# I2C-7-Segment-Backpack-dot8inch.net
KiCad netlist of a schematic drawn in EAGLE
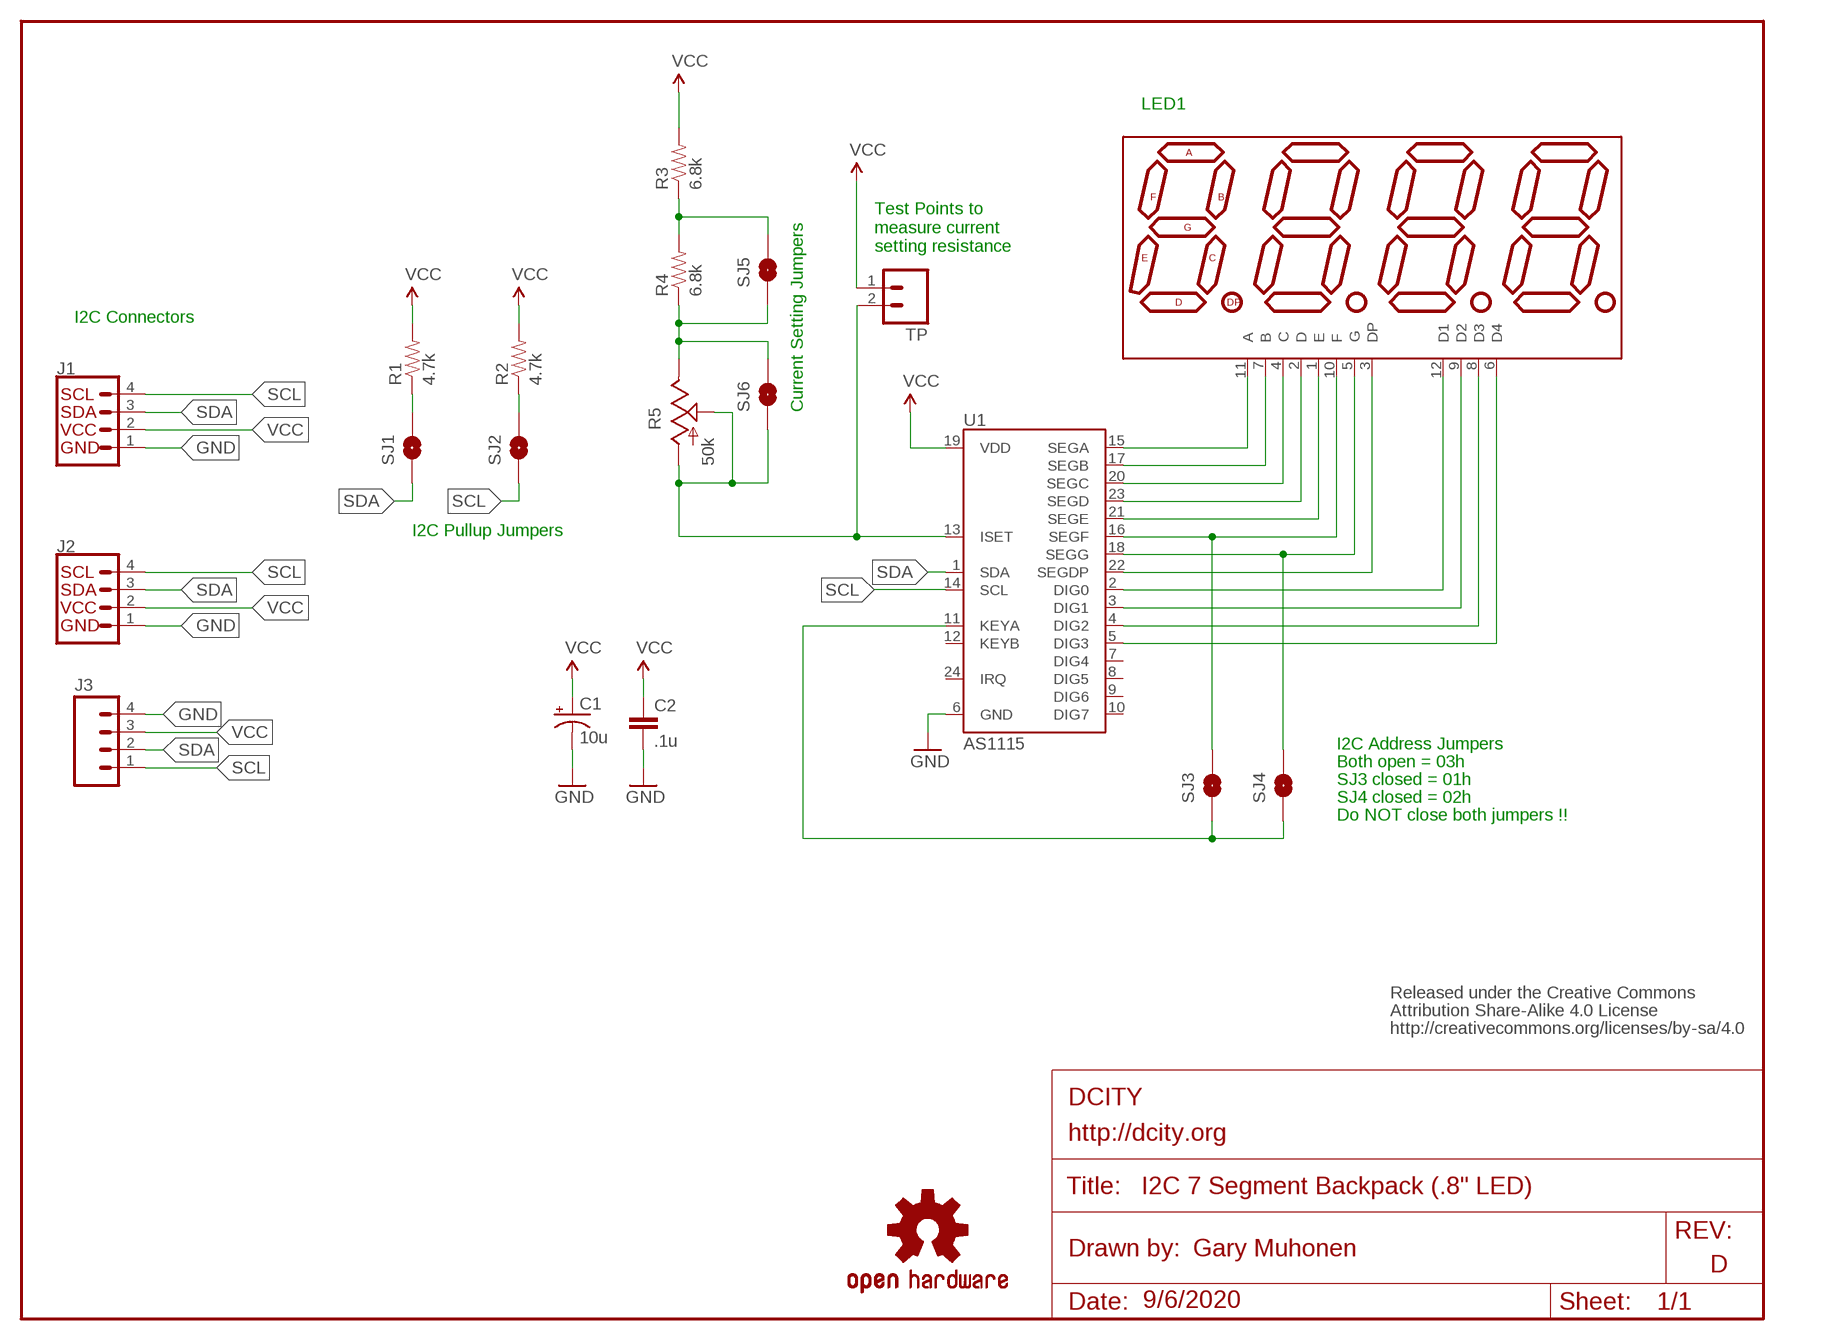
[diagram p0: schematic, sheet 1]

(export (version "E")
  (design (tool "Eeschema 10.0.6"))
  (components
    (comp (ref "C1")
      (value "10u")
      (footprint "eagle-import:0805-POL")
      (libsource (lib "eagle-import") (part "CAP_POL0805"))
    )
    (comp (ref "C2")
      (value ".1u")
      (footprint "eagle-import:0805-CAP")
      (libsource (lib "eagle-import") (part "CAP0805"))
    )
    (comp (ref "DISP1")
      (value "LED1")
      (footprint "eagle-import:7-SEGMENT-4DIGIT-COUNTER-NO-SILK")
      (libsource (lib "eagle-import") (part "7-SEGMENT-4DIGIT-COUNTER"))
    )
    (comp (ref "J1")
      (value "QWIIC_RIGHT_ANGLE")
      (footprint "eagle-import:JST04_1MM_RA")
      (libsource (lib "eagle-import") (part "QWIIC_CONNECTORJS-1MM"))
    )
    (comp (ref "J2")
      (value "QWIIC_RIGHT_ANGLE")
      (footprint "eagle-import:JST04_1MM_RA")
      (libsource (lib "eagle-import") (part "QWIIC_CONNECTORJS-1MM"))
    )
    (comp (ref "J3")
      (value "M04LOCK")
      (footprint "eagle-import:1X04_LOCK")
      (libsource (lib "eagle-import") (part "M04LOCK"))
    )
    (comp (ref "LOGO1")
      (value "OSHW-LOGOS")
      (footprint "eagle-import:OSHW-LOGO-S")
      (libsource (lib "eagle-import") (part "OSHW-LOGOS"))
    )
    (comp (ref "R1")
      (value "4.7k")
      (footprint "eagle-import:0805-RES")
      (libsource (lib "eagle-import") (part "RESISTOR0805"))
    )
    (comp (ref "R2")
      (value "4.7k")
      (footprint "eagle-import:0805-RES")
      (libsource (lib "eagle-import") (part "RESISTOR0805"))
    )
    (comp (ref "R3")
      (value "6.8k")
      (footprint "eagle-import:0805-RES")
      (libsource (lib "eagle-import") (part "RESISTOR0805"))
    )
    (comp (ref "R4")
      (value "6.8k")
      (footprint "eagle-import:0805-RES")
      (libsource (lib "eagle-import") (part "RESISTOR0805"))
    )
    (comp (ref "R5")
      (value "50k")
      (footprint "eagle-import:POT-TC33X")
      (libsource (lib "eagle-import") (part "POT-TC33X"))
    )
    (comp (ref "SJ1")
      (value "SOLDERJUMPERNO")
      (footprint "eagle-import:SJ_2S-NO")
      (libsource (lib "eagle-import") (part "SOLDERJUMPERNO"))
    )
    (comp (ref "SJ2")
      (value "SOLDERJUMPERNO")
      (footprint "eagle-import:SJ_2S-NO")
      (libsource (lib "eagle-import") (part "SOLDERJUMPERNO"))
    )
    (comp (ref "SJ3")
      (value "SOLDERJUMPERNO")
      (footprint "eagle-import:SJ_2S-NO")
      (libsource (lib "eagle-import") (part "SOLDERJUMPERNO"))
    )
    (comp (ref "SJ4")
      (value "SOLDERJUMPERNO")
      (footprint "eagle-import:SJ_2S-NO")
      (libsource (lib "eagle-import") (part "SOLDERJUMPERNO"))
    )
    (comp (ref "SJ5")
      (value "SOLDERJUMPERNO")
      (footprint "eagle-import:SJ_2S-NO")
      (libsource (lib "eagle-import") (part "SOLDERJUMPERNO"))
    )
    (comp (ref "SJ6")
      (value "SOLDERJUMPERNO")
      (footprint "eagle-import:SJ_2S-NO")
      (libsource (lib "eagle-import") (part "SOLDERJUMPERNO"))
    )
    (comp (ref "TP")
      (value "M02PTH")
      (footprint "eagle-import:1X02")
      (libsource (lib "eagle-import") (part "M02PTH"))
    )
    (comp (ref "U$2")
      (value "CREATIVE_COMMONS")
      (footprint "eagle-import:CREATIVE_COMMONS")
      (libsource (lib "eagle-import") (part "CREATIVE_COMMONS"))
    )
    (comp (ref "U1")
      (value "AS1115")
      (footprint "eagle-import:TSSOP-24")
      (libsource (lib "eagle-import") (part "AS1115-LP"))
    )
  )
  (nets
    (net (code "1") (name "GND") (class "Default")
      (node (ref "C1") (pin "-") (pinfunction "-_-") (pintype "passive"))
      (node (ref "C2") (pin "2") (pinfunction "2_2") (pintype "passive"))
      (node (ref "J1") (pin "1") (pinfunction "1_1") (pintype "power_in"))
      (node (ref "J2") (pin "1") (pinfunction "1_1") (pintype "power_in"))
      (node (ref "J3") (pin "4") (pinfunction "4_4") (pintype "passive"))
      (node (ref "U1") (pin "6") (pinfunction "GND_6") (pintype "bidirectional"))
    )
    (net (code "2") (name "Net-(DISP1-A)") (class "Default")
      (node (ref "DISP1") (pin "11") (pinfunction "A_11") (pintype "bidirectional"))
      (node (ref "U1") (pin "15") (pinfunction "SEGA_15") (pintype "bidirectional"))
    )
    (net (code "3") (name "Net-(DISP1-B)") (class "Default")
      (node (ref "DISP1") (pin "7") (pinfunction "B_7") (pintype "bidirectional"))
      (node (ref "U1") (pin "17") (pinfunction "SEGB_17") (pintype "bidirectional"))
    )
    (net (code "4") (name "Net-(DISP1-C)") (class "Default")
      (node (ref "DISP1") (pin "4") (pinfunction "C_4") (pintype "bidirectional"))
      (node (ref "U1") (pin "20") (pinfunction "SEGC_20") (pintype "bidirectional"))
    )
    (net (code "5") (name "Net-(DISP1-D)") (class "Default")
      (node (ref "DISP1") (pin "2") (pinfunction "D_2") (pintype "bidirectional"))
      (node (ref "U1") (pin "23") (pinfunction "SEGD_23") (pintype "bidirectional"))
    )
    (net (code "6") (name "Net-(DISP1-D1)") (class "Default")
      (node (ref "DISP1") (pin "12") (pinfunction "D1_12") (pintype "bidirectional"))
      (node (ref "U1") (pin "2") (pinfunction "DIG0_2") (pintype "bidirectional"))
    )
    (net (code "7") (name "Net-(DISP1-D2)") (class "Default")
      (node (ref "DISP1") (pin "9") (pinfunction "D2_9") (pintype "bidirectional"))
      (node (ref "U1") (pin "3") (pinfunction "DIG1_3") (pintype "bidirectional"))
    )
    (net (code "8") (name "Net-(DISP1-D3)") (class "Default")
      (node (ref "DISP1") (pin "8") (pinfunction "D3_8") (pintype "bidirectional"))
      (node (ref "U1") (pin "4") (pinfunction "DIG2_4") (pintype "bidirectional"))
    )
    (net (code "9") (name "Net-(DISP1-D4)") (class "Default")
      (node (ref "DISP1") (pin "6") (pinfunction "D4_6") (pintype "bidirectional"))
      (node (ref "U1") (pin "5") (pinfunction "DIG3_5") (pintype "bidirectional"))
    )
    (net (code "10") (name "Net-(DISP1-DP)") (class "Default")
      (node (ref "DISP1") (pin "3") (pinfunction "DP_3") (pintype "bidirectional"))
      (node (ref "U1") (pin "22") (pinfunction "SEGDP_22") (pintype "bidirectional"))
    )
    (net (code "11") (name "Net-(DISP1-E)") (class "Default")
      (node (ref "DISP1") (pin "1") (pinfunction "E_1") (pintype "bidirectional"))
      (node (ref "U1") (pin "21") (pinfunction "SEGE_21") (pintype "bidirectional"))
    )
    (net (code "12") (name "Net-(DISP1-F)") (class "Default")
      (node (ref "DISP1") (pin "10") (pinfunction "F_10") (pintype "bidirectional"))
      (node (ref "SJ3") (pin "2") (pinfunction "2_2") (pintype "passive"))
      (node (ref "U1") (pin "16") (pinfunction "SEGF_16") (pintype "bidirectional"))
    )
    (net (code "13") (name "Net-(DISP1-G)") (class "Default")
      (node (ref "DISP1") (pin "5") (pinfunction "G_5") (pintype "bidirectional"))
      (node (ref "SJ4") (pin "2") (pinfunction "2_2") (pintype "passive"))
      (node (ref "U1") (pin "18") (pinfunction "SEGG_18") (pintype "bidirectional"))
    )
    (net (code "14") (name "Net-(R1-Pad1)") (class "Default")
      (node (ref "R1") (pin "1") (pinfunction "1_1") (pintype "passive"))
      (node (ref "SJ1") (pin "2") (pinfunction "2_2") (pintype "passive"))
    )
    (net (code "15") (name "Net-(R2-Pad1)") (class "Default")
      (node (ref "R2") (pin "1") (pinfunction "1_1") (pintype "passive"))
      (node (ref "SJ2") (pin "2") (pinfunction "2_2") (pintype "passive"))
    )
    (net (code "16") (name "Net-(R3-Pad1)") (class "Default")
      (node (ref "R3") (pin "1") (pinfunction "1_1") (pintype "passive"))
      (node (ref "R4") (pin "2") (pinfunction "2_2") (pintype "passive"))
      (node (ref "SJ5") (pin "2") (pinfunction "2_2") (pintype "passive"))
    )
    (net (code "17") (name "Net-(R5-A)") (class "Default")
      (node (ref "R5") (pin "1") (pinfunction "A_1") (pintype "passive"))
      (node (ref "R5") (pin "2") (pinfunction "S_2") (pintype "passive"))
      (node (ref "SJ6") (pin "1") (pinfunction "1_1") (pintype "passive"))
      (node (ref "TP") (pin "2") (pinfunction "2_2") (pintype "passive"))
      (node (ref "U1") (pin "13") (pinfunction "ISET_13") (pintype "bidirectional"))
    )
    (net (code "18") (name "Net-(R5-E)") (class "Default")
      (node (ref "R4") (pin "1") (pinfunction "1_1") (pintype "passive"))
      (node (ref "R5") (pin "3") (pinfunction "E_3") (pintype "passive"))
      (node (ref "SJ5") (pin "1") (pinfunction "1_1") (pintype "passive"))
      (node (ref "SJ6") (pin "2") (pinfunction "2_2") (pintype "passive"))
    )
    (net (code "19") (name "Net-(U1-KEYA)") (class "Default")
      (node (ref "SJ3") (pin "1") (pinfunction "1_1") (pintype "passive"))
      (node (ref "SJ4") (pin "1") (pinfunction "1_1") (pintype "passive"))
      (node (ref "U1") (pin "11") (pinfunction "KEYA_11") (pintype "bidirectional"))
    )
    (net (code "20") (name "SCL") (class "Default")
      (node (ref "J1") (pin "4") (pinfunction "4_4") (pintype "passive"))
      (node (ref "J2") (pin "4") (pinfunction "4_4") (pintype "passive"))
      (node (ref "J3") (pin "1") (pinfunction "1_1") (pintype "passive"))
      (node (ref "SJ2") (pin "1") (pinfunction "1_1") (pintype "passive"))
      (node (ref "U1") (pin "14") (pinfunction "SCL_14") (pintype "bidirectional"))
    )
    (net (code "21") (name "SDA") (class "Default")
      (node (ref "J1") (pin "3") (pinfunction "3_3") (pintype "passive"))
      (node (ref "J2") (pin "3") (pinfunction "3_3") (pintype "passive"))
      (node (ref "J3") (pin "2") (pinfunction "2_2") (pintype "passive"))
      (node (ref "SJ1") (pin "1") (pinfunction "1_1") (pintype "passive"))
      (node (ref "U1") (pin "1") (pinfunction "SDA_1") (pintype "bidirectional"))
    )
    (net (code "22") (name "VCC") (class "Default")
      (node (ref "C1") (pin "+") (pinfunction "+_+") (pintype "passive"))
      (node (ref "C2") (pin "1") (pinfunction "1_1") (pintype "passive"))
      (node (ref "J1") (pin "2") (pinfunction "2_2") (pintype "power_in"))
      (node (ref "J2") (pin "2") (pinfunction "2_2") (pintype "power_in"))
      (node (ref "J3") (pin "3") (pinfunction "3_3") (pintype "passive"))
      (node (ref "R1") (pin "2") (pinfunction "2_2") (pintype "passive"))
      (node (ref "R2") (pin "2") (pinfunction "2_2") (pintype "passive"))
      (node (ref "R3") (pin "2") (pinfunction "2_2") (pintype "passive"))
      (node (ref "TP") (pin "1") (pinfunction "1_1") (pintype "passive"))
      (node (ref "U1") (pin "19") (pinfunction "VDD_19") (pintype "bidirectional"))
    )
    (net (code "23") (name "unconnected-(U1-DIG4-Pad7)") (class "Default")
      (node (ref "U1") (pin "7") (pinfunction "DIG4_7") (pintype "bidirectional"))
    )
    (net (code "24") (name "unconnected-(U1-DIG5-Pad8)") (class "Default")
      (node (ref "U1") (pin "8") (pinfunction "DIG5_8") (pintype "bidirectional"))
    )
    (net (code "25") (name "unconnected-(U1-DIG6-Pad9)") (class "Default")
      (node (ref "U1") (pin "9") (pinfunction "DIG6_9") (pintype "bidirectional"))
    )
    (net (code "26") (name "unconnected-(U1-DIG7-Pad10)") (class "Default")
      (node (ref "U1") (pin "10") (pinfunction "DIG7_10") (pintype "bidirectional"))
    )
    (net (code "27") (name "unconnected-(U1-IRQ-Pad24)") (class "Default")
      (node (ref "U1") (pin "24") (pinfunction "IRQ_24") (pintype "bidirectional"))
    )
    (net (code "28") (name "unconnected-(U1-KEYB-Pad12)") (class "Default")
      (node (ref "U1") (pin "12") (pinfunction "KEYB_12") (pintype "bidirectional"))
    )
  )
)
